# GSR_REV_1_0.net
KiCad netlist of a schematic drawn in EAGLE
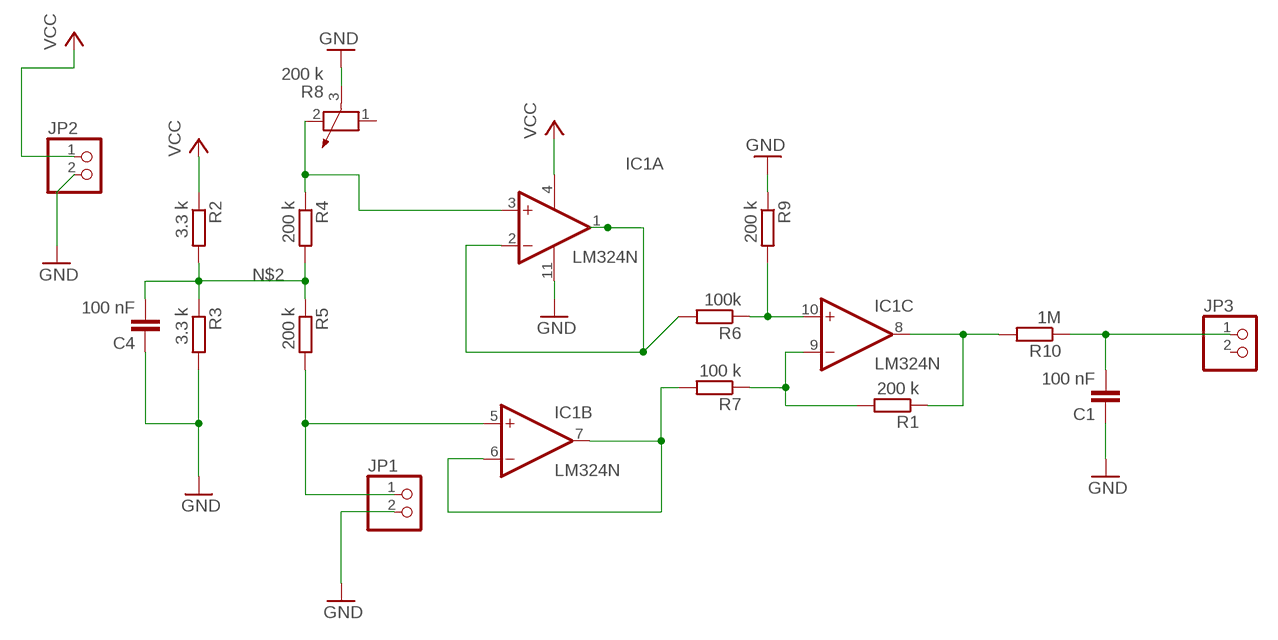
[diagram p0: schematic, sheet 1]

(export (version "E")
  (design (tool "Eeschema 10.0.6"))
  (components
    (comp (ref "C1")
      (value "100 nF")
      (footprint "eagle-import:C025-025X050")
      (libsource (lib "eagle-import") (part "C-EU025-025X050"))
    )
    (comp (ref "C4")
      (value "100 nF")
      (footprint "eagle-import:C025-025X050")
      (libsource (lib "eagle-import") (part "C-EU025-025X050"))
    )
    (comp (ref "IC1")
      (value "LM324N")
      (footprint "eagle-import:DIL14")
      (libsource (lib "eagle-import") (part "LM324N"))
    )
    (comp (ref "JP1")
      (value "PINHD-1X2")
      (footprint "eagle-import:1X02")
      (libsource (lib "eagle-import") (part "PINHD-1X2"))
    )
    (comp (ref "JP2")
      (value "PINHD-1X2")
      (footprint "eagle-import:1X02")
      (libsource (lib "eagle-import") (part "PINHD-1X2"))
    )
    (comp (ref "JP3")
      (value "PINHD-1X2")
      (footprint "eagle-import:1X02")
      (libsource (lib "eagle-import") (part "PINHD-1X2"))
    )
    (comp (ref "R1")
      (value "200 k")
      (footprint "eagle-import:0207_12")
      (libsource (lib "eagle-import") (part "R-EU_0207/12"))
    )
    (comp (ref "R2")
      (value "3.3 k")
      (footprint "eagle-import:0207_12")
      (libsource (lib "eagle-import") (part "R-EU_0207/12"))
    )
    (comp (ref "R3")
      (value "3.3 k")
      (footprint "eagle-import:0207_12")
      (libsource (lib "eagle-import") (part "R-EU_0207/12"))
    )
    (comp (ref "R4")
      (value "200 k")
      (footprint "eagle-import:0207_12")
      (libsource (lib "eagle-import") (part "R-EU_0207/12"))
    )
    (comp (ref "R5")
      (value "200 k")
      (footprint "eagle-import:0207_12")
      (libsource (lib "eagle-import") (part "R-EU_0207/12"))
    )
    (comp (ref "R6")
      (value "100k")
      (footprint "eagle-import:0207_12")
      (libsource (lib "eagle-import") (part "R-EU_0207/12"))
    )
    (comp (ref "R7")
      (value "100 k")
      (footprint "eagle-import:0207_12")
      (libsource (lib "eagle-import") (part "R-EU_0207/12"))
    )
    (comp (ref "R8")
      (value "200 k")
      (footprint "eagle-import:PT-10")
      (libsource (lib "eagle-import") (part "POTENTIOMETER_PT-10"))
    )
    (comp (ref "R9")
      (value "200 k")
      (footprint "eagle-import:0207_12")
      (libsource (lib "eagle-import") (part "R-EU_0207/12"))
    )
    (comp (ref "R10")
      (value "1M")
      (footprint "eagle-import:0207_12")
      (libsource (lib "eagle-import") (part "R-EU_0207/12"))
    )
  )
  (nets
    (net (code "1") (name "/N$2") (class "Default")
      (node (ref "C4") (pin "2") (pinfunction "2_2") (pintype "passive"))
      (node (ref "R2") (pin "2") (pinfunction "2_2") (pintype "passive"))
      (node (ref "R3") (pin "1") (pinfunction "1_1") (pintype "passive"))
      (node (ref "R4") (pin "2") (pinfunction "2_2") (pintype "passive"))
      (node (ref "R5") (pin "1") (pinfunction "1_1") (pintype "passive"))
    )
    (net (code "2") (name "GND") (class "Default")
      (node (ref "C1") (pin "1") (pinfunction "1_1") (pintype "passive"))
      (node (ref "C4") (pin "1") (pinfunction "1_1") (pintype "passive"))
      (node (ref "IC1") (pin "11") (pinfunction "V-_11") (pintype "power_in"))
      (node (ref "JP1") (pin "2") (pinfunction "2_2") (pintype "passive"))
      (node (ref "JP2") (pin "2") (pinfunction "2_2") (pintype "passive"))
      (node (ref "R3") (pin "2") (pinfunction "2_2") (pintype "passive"))
      (node (ref "R8") (pin "3") (pinfunction "3_3") (pintype "passive"))
      (node (ref "R9") (pin "1") (pinfunction "1_1") (pintype "passive"))
    )
    (net (code "3") (name "Net-(C1-Pad2)") (class "Default")
      (node (ref "C1") (pin "2") (pinfunction "2_2") (pintype "passive"))
      (node (ref "JP3") (pin "1") (pinfunction "1_1") (pintype "passive"))
      (node (ref "R10") (pin "1") (pinfunction "1_1") (pintype "passive"))
    )
    (net (code "4") (name "Net-(IC1A-+IN)") (class "Default")
      (node (ref "IC1") (pin "3") (pinfunction "+IN_3") (pintype "input"))
      (node (ref "R4") (pin "1") (pinfunction "1_1") (pintype "passive"))
      (node (ref "R8") (pin "2") (pinfunction "2_2") (pintype "passive"))
    )
    (net (code "5") (name "Net-(IC1A--IN)") (class "Default")
      (node (ref "IC1") (pin "1") (pinfunction "OUT_1") (pintype "output"))
      (node (ref "IC1") (pin "2") (pinfunction "-IN_2") (pintype "input"))
      (node (ref "R6") (pin "2") (pinfunction "2_2") (pintype "passive"))
    )
    (net (code "6") (name "Net-(IC1B-+IN)") (class "Default")
      (node (ref "IC1") (pin "5") (pinfunction "+IN_5") (pintype "input"))
      (node (ref "JP1") (pin "1") (pinfunction "1_1") (pintype "passive"))
      (node (ref "R5") (pin "2") (pinfunction "2_2") (pintype "passive"))
    )
    (net (code "7") (name "Net-(IC1B--IN)") (class "Default")
      (node (ref "IC1") (pin "6") (pinfunction "-IN_6") (pintype "input"))
      (node (ref "IC1") (pin "7") (pinfunction "OUT_7") (pintype "output"))
      (node (ref "R7") (pin "2") (pinfunction "2_2") (pintype "passive"))
    )
    (net (code "8") (name "Net-(IC1C-+IN)") (class "Default")
      (node (ref "IC1") (pin "10") (pinfunction "+IN_10") (pintype "input"))
      (node (ref "R6") (pin "1") (pinfunction "1_1") (pintype "passive"))
      (node (ref "R9") (pin "2") (pinfunction "2_2") (pintype "passive"))
    )
    (net (code "9") (name "Net-(IC1C--IN)") (class "Default")
      (node (ref "IC1") (pin "9") (pinfunction "-IN_9") (pintype "input"))
      (node (ref "R1") (pin "2") (pinfunction "2_2") (pintype "passive"))
      (node (ref "R7") (pin "1") (pinfunction "1_1") (pintype "passive"))
    )
    (net (code "10") (name "Net-(IC1C-OUT)") (class "Default")
      (node (ref "IC1") (pin "8") (pinfunction "OUT_8") (pintype "output"))
      (node (ref "R1") (pin "1") (pinfunction "1_1") (pintype "passive"))
      (node (ref "R10") (pin "2") (pinfunction "2_2") (pintype "passive"))
    )
    (net (code "11") (name "VCC") (class "Default")
      (node (ref "IC1") (pin "4") (pinfunction "V+_4") (pintype "power_in"))
      (node (ref "JP2") (pin "1") (pinfunction "1_1") (pintype "passive"))
      (node (ref "R2") (pin "1") (pinfunction "1_1") (pintype "passive"))
    )
    (net (code "12") (name "unconnected-(JP3-Pad2)") (class "Default")
      (node (ref "JP3") (pin "2") (pinfunction "2_2") (pintype "passive"))
    )
    (net (code "13") (name "unconnected-(R8-Pad1)") (class "Default")
      (node (ref "R8") (pin "1") (pinfunction "1_1") (pintype "passive"))
    )
  )
)
